# Electronic_DC_Load.net
KiCad netlist of a schematic drawn in EAGLE
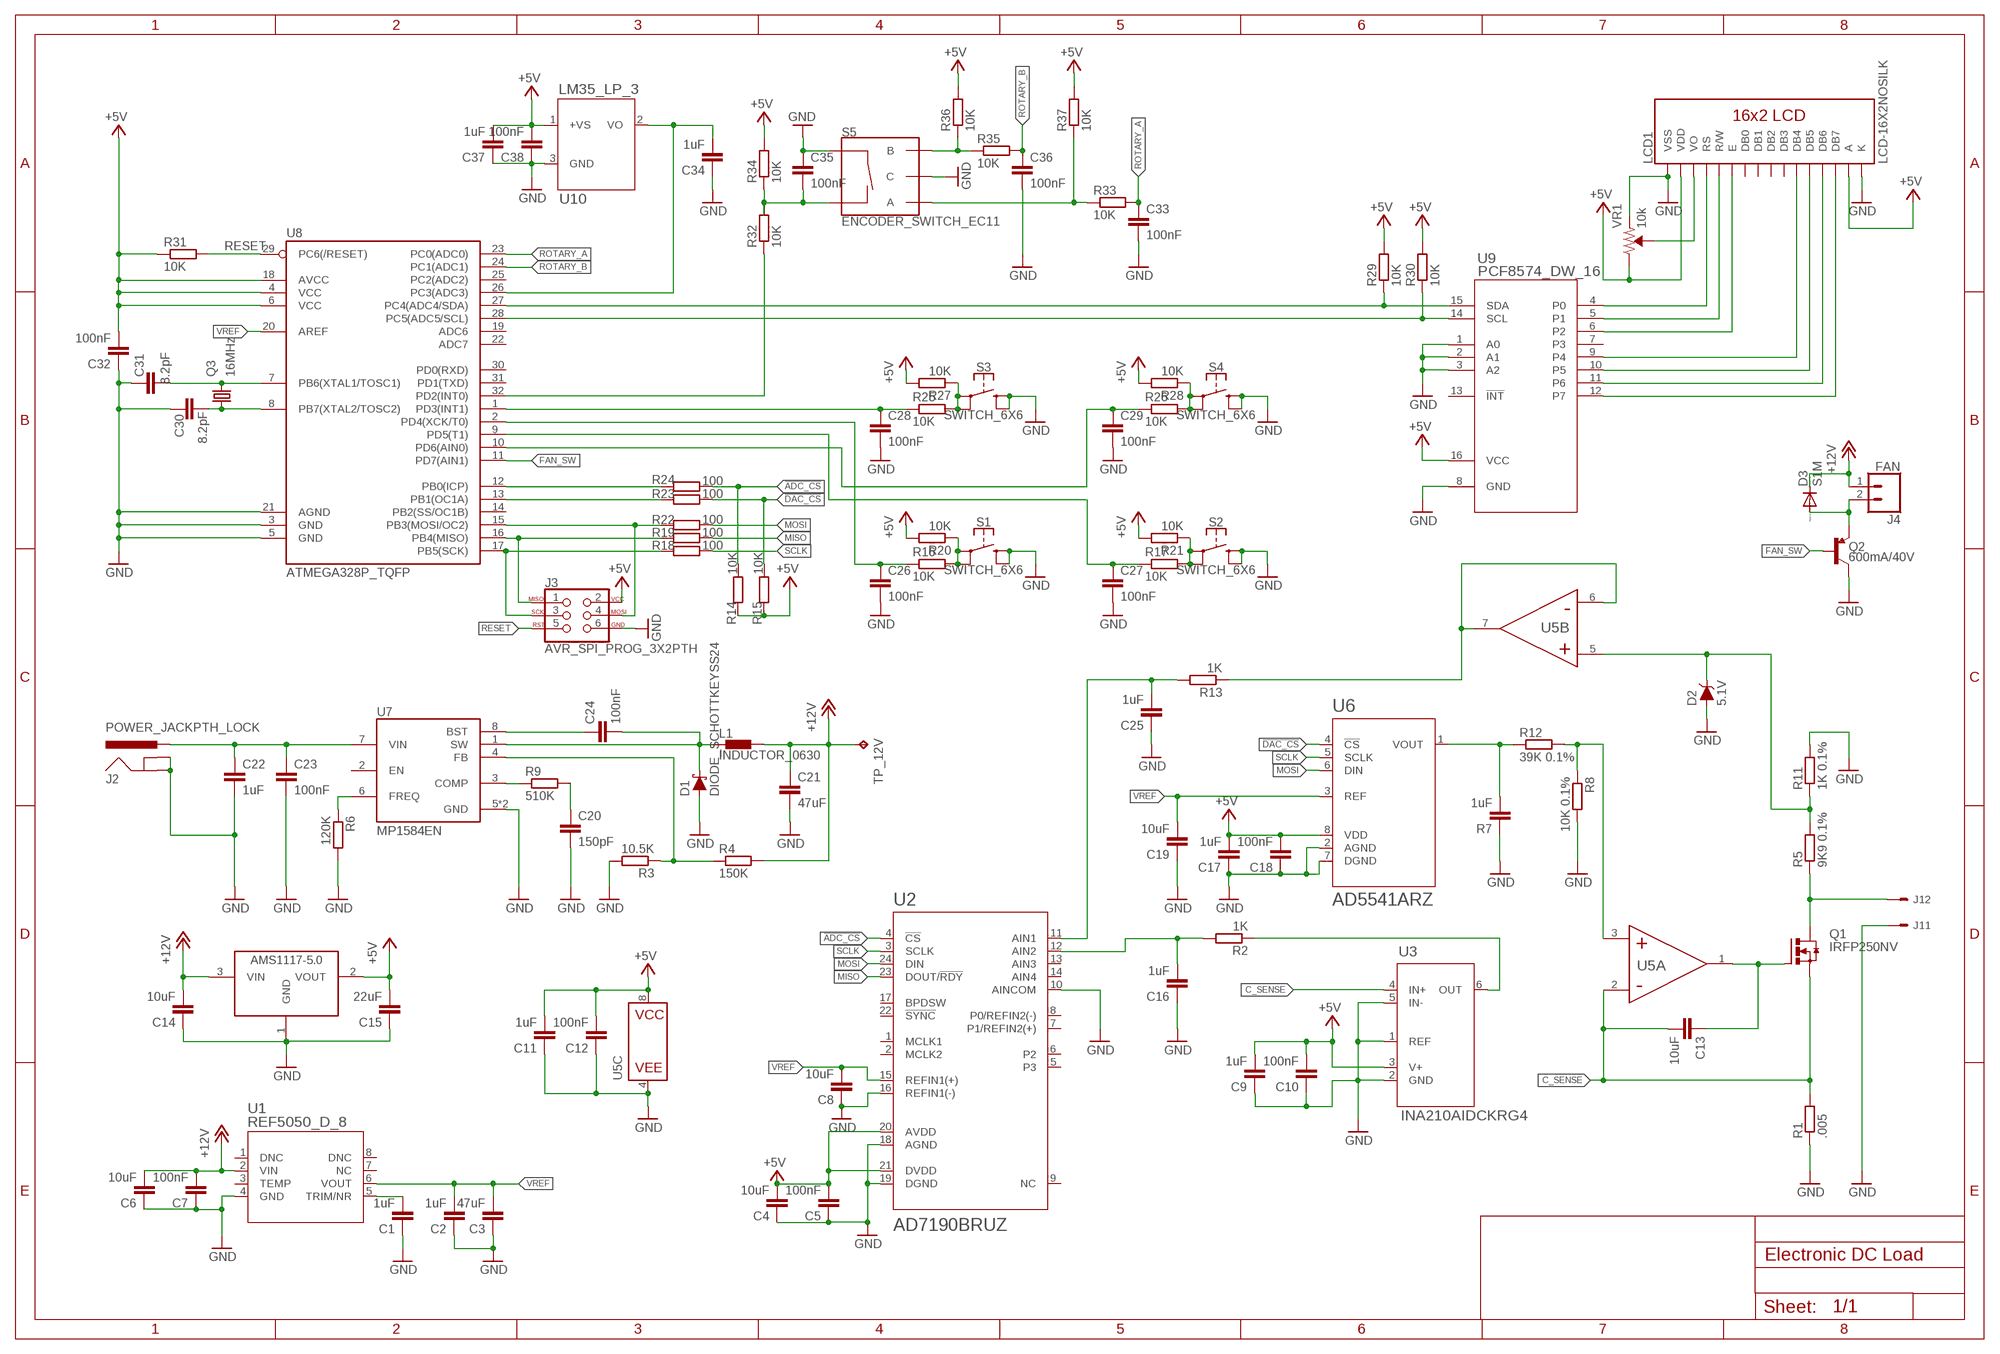
[diagram p0: schematic, sheet 1]

(export (version "E")
  (design (tool "Eeschema 10.0.6"))
  (components
    (comp (ref "C1")
      (value "1uF")
      (footprint "eagle-import:C0805")
      (libsource (lib "eagle-import") (part "C-EUC0805"))
    )
    (comp (ref "C2")
      (value "1uF")
      (footprint "eagle-import:C0805")
      (libsource (lib "eagle-import") (part "C-EUC0805"))
    )
    (comp (ref "C3")
      (value "47uF")
      (footprint "eagle-import:C1206")
      (libsource (lib "eagle-import") (part "C-EUC1206"))
    )
    (comp (ref "C4")
      (value "10uF")
      (footprint "eagle-import:C1206")
      (libsource (lib "eagle-import") (part "C-EUC1206"))
    )
    (comp (ref "C5")
      (value "100nF")
      (footprint "eagle-import:C0805")
      (libsource (lib "eagle-import") (part "C-EUC0805"))
    )
    (comp (ref "C6")
      (value "10uF")
      (footprint "eagle-import:C1206")
      (libsource (lib "eagle-import") (part "C-EUC1206"))
    )
    (comp (ref "C7")
      (value "100nF")
      (footprint "eagle-import:C0805")
      (libsource (lib "eagle-import") (part "C-EUC0805"))
    )
    (comp (ref "C8")
      (value "10uF")
      (footprint "eagle-import:C1206")
      (libsource (lib "eagle-import") (part "C-EUC1206"))
    )
    (comp (ref "C9")
      (value "1uF")
      (footprint "eagle-import:C0805")
      (libsource (lib "eagle-import") (part "C-EUC0805"))
    )
    (comp (ref "C10")
      (value "100nF")
      (footprint "eagle-import:C0805")
      (libsource (lib "eagle-import") (part "C-EUC0805"))
    )
    (comp (ref "C11")
      (value "1uF")
      (footprint "eagle-import:C0805")
      (libsource (lib "eagle-import") (part "C-EUC0805"))
    )
    (comp (ref "C12")
      (value "100nF")
      (footprint "eagle-import:C0805")
      (libsource (lib "eagle-import") (part "C-EUC0805"))
    )
    (comp (ref "C13")
      (value "10uF")
      (footprint "eagle-import:C1206")
      (libsource (lib "eagle-import") (part "C-EUC1206"))
    )
    (comp (ref "C14")
      (value "10uF")
      (footprint "eagle-import:C1206")
      (libsource (lib "eagle-import") (part "C-EUC1206"))
    )
    (comp (ref "C15")
      (value "22uF")
      (footprint "eagle-import:C1206")
      (libsource (lib "eagle-import") (part "C-EUC1206"))
    )
    (comp (ref "C16")
      (value "1uF")
      (footprint "eagle-import:C0805")
      (libsource (lib "eagle-import") (part "C-EUC0805"))
    )
    (comp (ref "C17")
      (value "1uF")
      (footprint "eagle-import:C0805")
      (libsource (lib "eagle-import") (part "C-EUC0805"))
    )
    (comp (ref "C18")
      (value "100nF")
      (footprint "eagle-import:C0805")
      (libsource (lib "eagle-import") (part "C-EUC0805"))
    )
    (comp (ref "C19")
      (value "10uF")
      (footprint "eagle-import:C1206")
      (libsource (lib "eagle-import") (part "C-EUC1206"))
    )
    (comp (ref "C20")
      (value "150pF")
      (footprint "eagle-import:C0402")
      (libsource (lib "eagle-import") (part "C-EUC0402"))
    )
    (comp (ref "C21")
      (value "47uF")
      (footprint "eagle-import:C1206")
      (libsource (lib "eagle-import") (part "C-EUC1206"))
    )
    (comp (ref "C22")
      (value "1uF")
      (footprint "eagle-import:C0805")
      (libsource (lib "eagle-import") (part "C-EUC0805"))
    )
    (comp (ref "C23")
      (value "100nF")
      (footprint "eagle-import:C0805")
      (libsource (lib "eagle-import") (part "C-EUC0805"))
    )
    (comp (ref "C24")
      (value "100nF")
      (footprint "eagle-import:C0805")
      (libsource (lib "eagle-import") (part "C-EUC0805"))
    )
    (comp (ref "C25")
      (value "1uF")
      (footprint "eagle-import:C0805")
      (libsource (lib "eagle-import") (part "C-EUC0805"))
    )
    (comp (ref "C26")
      (value "100nF")
      (footprint "eagle-import:C0603")
      (libsource (lib "eagle-import") (part "C-EUC0603"))
    )
    (comp (ref "C27")
      (value "100nF")
      (footprint "eagle-import:C0603")
      (libsource (lib "eagle-import") (part "C-EUC0603"))
    )
    (comp (ref "C28")
      (value "100nF")
      (footprint "eagle-import:C0603")
      (libsource (lib "eagle-import") (part "C-EUC0603"))
    )
    (comp (ref "C29")
      (value "100nF")
      (footprint "eagle-import:C0603")
      (libsource (lib "eagle-import") (part "C-EUC0603"))
    )
    (comp (ref "C30")
      (value "8.2pF")
      (footprint "eagle-import:C0603")
      (libsource (lib "eagle-import") (part "C-EUC0603"))
    )
    (comp (ref "C31")
      (value "8.2pF")
      (footprint "eagle-import:C0603")
      (libsource (lib "eagle-import") (part "C-EUC0603"))
    )
    (comp (ref "C32")
      (value "100nF")
      (footprint "eagle-import:C0603")
      (libsource (lib "eagle-import") (part "C-EUC0603"))
    )
    (comp (ref "C33")
      (value "100nF")
      (footprint "eagle-import:C0603")
      (libsource (lib "eagle-import") (part "C-EUC0603"))
    )
    (comp (ref "C34")
      (value "1uF")
      (footprint "eagle-import:C0805")
      (libsource (lib "eagle-import") (part "C-EUC0805"))
    )
    (comp (ref "C35")
      (value "100nF")
      (footprint "eagle-import:C0603")
      (libsource (lib "eagle-import") (part "C-EUC0603"))
    )
    (comp (ref "C36")
      (value "100nF")
      (footprint "eagle-import:C0603")
      (libsource (lib "eagle-import") (part "C-EUC0603"))
    )
    (comp (ref "C37")
      (value "1uF")
      (footprint "eagle-import:C0805")
      (libsource (lib "eagle-import") (part "C-EUC0805"))
    )
    (comp (ref "C38")
      (value "100nF")
      (footprint "eagle-import:C0805")
      (libsource (lib "eagle-import") (part "C-EUC0805"))
    )
    (comp (ref "D1")
      (value "DIODE_SCHOTTKEYSS24")
      (footprint "eagle-import:SMA-DIODE")
      (libsource (lib "eagle-import") (part "DIODE_SCHOTTKEYSS24"))
    )
    (comp (ref "D2")
      (value "5.1V")
      (footprint "eagle-import:LL-34")
      (libsource (lib "eagle-import") (part "DIODE-ZENER-ZMM5.1"))
    )
    (comp (ref "D3")
      (value "S1M")
      (footprint "eagle-import:SMA")
      (libsource (lib "eagle-import") (part "S1M"))
    )
    (comp (ref "J1")
      (value "KF762-2")
      (footprint "eagle-import:KF762-2")
      (libsource (lib "eagle-import") (part "KF762-2"))
    )
    (comp (ref "J2")
      (value "POWER_JACKPTH_LOCK")
      (footprint "eagle-import:POWER_JACK_PTH_LOCK")
      (libsource (lib "eagle-import") (part "POWER_JACKPTH_LOCK"))
    )
    (comp (ref "J3")
      (value "AVR_SPI_PROG_3X2PTH")
      (footprint "eagle-import:2X3")
      (libsource (lib "eagle-import") (part "AVR_SPI_PROG_3X2PTH"))
    )
    (comp (ref "J4")
      (value "FAN")
      (footprint "eagle-import:1X02_LOCK_LONGPADS")
      (libsource (lib "eagle-import") (part "CONN_02LOCK_LONGPADS"))
    )
    (comp (ref "L1")
      (value "INDUCTOR_0630")
      (footprint "eagle-import:INDUCTOR_0630")
      (libsource (lib "eagle-import") (part "INDUCTOR_0630"))
    )
    (comp (ref "LCD1")
      (value "LCD-16X2NOSILK")
      (footprint "eagle-import:LCD-16X2_NOSILK")
      (libsource (lib "eagle-import") (part "LCD-16X2NOSILK"))
    )
    (comp (ref "Q1")
      (value "IRFP250NV")
      (footprint "eagle-import:TO247BV")
      (libsource (lib "eagle-import") (part "IRFP250NV"))
    )
    (comp (ref "Q2")
      (value "600mA/40V")
      (footprint "eagle-import:SOT23-3")
      (libsource (lib "eagle-import") (part "TRANS_PNP-MMBT4403"))
    )
    (comp (ref "Q3")
      (value "16MHz")
      (footprint "eagle-import:3.2X2.5_KX-7")
      (libsource (lib "eagle-import") (part "KX-7"))
    )
    (comp (ref "R1")
      (value ".005")
      (footprint "eagle-import:2728")
      (libsource (lib "eagle-import") (part "MRE_R005_4W_2728_1%"))
    )
    (comp (ref "R2")
      (value "1K")
      (footprint "eagle-import:R0805")
      (libsource (lib "eagle-import") (part "R-EU_R0805"))
    )
    (comp (ref "R3")
      (value "10.5K")
      (footprint "eagle-import:R0603")
      (libsource (lib "eagle-import") (part "R-EU_R0603"))
    )
    (comp (ref "R4")
      (value "150K")
      (footprint "eagle-import:R0603")
      (libsource (lib "eagle-import") (part "R-EU_R0603"))
    )
    (comp (ref "R5")
      (value "9K9 0.1%")
      (footprint "eagle-import:M0805")
      (libsource (lib "eagle-import") (part "R-EU_M0805"))
    )
    (comp (ref "R6")
      (value "120K")
      (footprint "eagle-import:R0603")
      (libsource (lib "eagle-import") (part "R-EU_R0603"))
    )
    (comp (ref "R7")
      (value "1uF")
      (footprint "eagle-import:C0805")
      (libsource (lib "eagle-import") (part "C-EUC0805"))
    )
    (comp (ref "R8")
      (value "10K 0.1%")
      (footprint "eagle-import:R0805")
      (libsource (lib "eagle-import") (part "R-EU_R0805"))
    )
    (comp (ref "R9")
      (value "510K")
      (footprint "eagle-import:R0603")
      (libsource (lib "eagle-import") (part "R-EU_R0603"))
    )
    (comp (ref "R11")
      (value "1K 0.1%")
      (footprint "eagle-import:M0805")
      (libsource (lib "eagle-import") (part "R-EU_M0805"))
    )
    (comp (ref "R12")
      (value "39K 0.1%")
      (footprint "eagle-import:R0805")
      (libsource (lib "eagle-import") (part "R-EU_R0805"))
    )
    (comp (ref "R13")
      (value "1K")
      (footprint "eagle-import:R0805")
      (libsource (lib "eagle-import") (part "R-EU_R0805"))
    )
    (comp (ref "R14")
      (value "10K")
      (footprint "eagle-import:M0805")
      (libsource (lib "eagle-import") (part "R-EU_M0805"))
    )
    (comp (ref "R15")
      (value "10K")
      (footprint "eagle-import:M0805")
      (libsource (lib "eagle-import") (part "R-EU_M0805"))
    )
    (comp (ref "R16")
      (value "10K")
      (footprint "eagle-import:R0603")
      (libsource (lib "eagle-import") (part "R-EU_R0603"))
    )
    (comp (ref "R17")
      (value "10K")
      (footprint "eagle-import:R0603")
      (libsource (lib "eagle-import") (part "R-EU_R0603"))
    )
    (comp (ref "R18")
      (value "100")
      (footprint "eagle-import:M0805")
      (libsource (lib "eagle-import") (part "R-EU_M0805"))
    )
    (comp (ref "R19")
      (value "100")
      (footprint "eagle-import:M0805")
      (libsource (lib "eagle-import") (part "R-EU_M0805"))
    )
    (comp (ref "R20")
      (value "10K")
      (footprint "eagle-import:R0603")
      (libsource (lib "eagle-import") (part "R-EU_R0603"))
    )
    (comp (ref "R21")
      (value "10K")
      (footprint "eagle-import:R0603")
      (libsource (lib "eagle-import") (part "R-EU_R0603"))
    )
    (comp (ref "R22")
      (value "100")
      (footprint "eagle-import:M0805")
      (libsource (lib "eagle-import") (part "R-EU_M0805"))
    )
    (comp (ref "R23")
      (value "100")
      (footprint "eagle-import:M0805")
      (libsource (lib "eagle-import") (part "R-EU_M0805"))
    )
    (comp (ref "R24")
      (value "100")
      (footprint "eagle-import:M0805")
      (libsource (lib "eagle-import") (part "R-EU_M0805"))
    )
    (comp (ref "R25")
      (value "10K")
      (footprint "eagle-import:R0603")
      (libsource (lib "eagle-import") (part "R-EU_R0603"))
    )
    (comp (ref "R26")
      (value "10K")
      (footprint "eagle-import:R0603")
      (libsource (lib "eagle-import") (part "R-EU_R0603"))
    )
    (comp (ref "R27")
      (value "10K")
      (footprint "eagle-import:R0603")
      (libsource (lib "eagle-import") (part "R-EU_R0603"))
    )
    (comp (ref "R28")
      (value "10K")
      (footprint "eagle-import:R0603")
      (libsource (lib "eagle-import") (part "R-EU_R0603"))
    )
    (comp (ref "R29")
      (value "10K")
      (footprint "eagle-import:R0603")
      (libsource (lib "eagle-import") (part "R-EU_R0603"))
    )
    (comp (ref "R30")
      (value "10K")
      (footprint "eagle-import:R0603")
      (libsource (lib "eagle-import") (part "R-EU_R0603"))
    )
    (comp (ref "R31")
      (value "10K")
      (footprint "eagle-import:R0603")
      (libsource (lib "eagle-import") (part "R-EU_R0603"))
    )
    (comp (ref "R32")
      (value "10K")
      (footprint "eagle-import:R0603")
      (libsource (lib "eagle-import") (part "R-EU_R0603"))
    )
    (comp (ref "R33")
      (value "10K")
      (footprint "eagle-import:R0603")
      (libsource (lib "eagle-import") (part "R-EU_R0603"))
    )
    (comp (ref "R34")
      (value "10K")
      (footprint "eagle-import:R0603")
      (libsource (lib "eagle-import") (part "R-EU_R0603"))
    )
    (comp (ref "R35")
      (value "10K")
      (footprint "eagle-import:R0603")
      (libsource (lib "eagle-import") (part "R-EU_R0603"))
    )
    (comp (ref "R36")
      (value "10K")
      (footprint "eagle-import:R0603")
      (libsource (lib "eagle-import") (part "R-EU_R0603"))
    )
    (comp (ref "R37")
      (value "10K")
      (footprint "eagle-import:R0603")
      (libsource (lib "eagle-import") (part "R-EU_R0603"))
    )
    (comp (ref "S1")
      (value "SWITCH_6X6")
      (footprint "eagle-import:SWITCH_SMD_6MM")
      (libsource (lib "eagle-import") (part "SWITCH_6X6"))
    )
    (comp (ref "S2")
      (value "SWITCH_6X6")
      (footprint "eagle-import:SWITCH_SMD_6MM")
      (libsource (lib "eagle-import") (part "SWITCH_6X6"))
    )
    (comp (ref "S3")
      (value "SWITCH_6X6")
      (footprint "eagle-import:SWITCH_SMD_6MM")
      (libsource (lib "eagle-import") (part "SWITCH_6X6"))
    )
    (comp (ref "S4")
      (value "SWITCH_6X6")
      (footprint "eagle-import:SWITCH_SMD_6MM")
      (libsource (lib "eagle-import") (part "SWITCH_6X6"))
    )
    (comp (ref "S5")
      (value "ENCODER_SWITCH_EC11")
      (footprint "eagle-import:ROTARY_ENCODER_EC11")
      (libsource (lib "eagle-import") (part "ENCODER_SWITCH_EC11"))
    )
    (comp (ref "TP_12V")
      (value "TPB1,27")
      (footprint "eagle-import:B1,27")
      (libsource (lib "eagle-import") (part "TPB1,27"))
    )
    (comp (ref "U1")
      (value "REF5050_D_8")
      (footprint "eagle-import:D8")
      (fields
        (field (name "GENERIC_PART_NUMBER") "REF5050")
        (field (name "MANUFACTURER") "Texas Instruments")
        (field (name "MANUFACTURER_PART_NUMBER") "ref5050_d_8")
      )
      (libsource (lib "eagle-import") (part "REF5050_D_8"))
    )
    (comp (ref "U2")
      (value "AD7190BRUZ")
      (footprint "eagle-import:RU_24")
      (fields (field (name "MANUFACTURER_PART_NUMBER") "AD7190BRUZREEL"))
      (libsource (lib "eagle-import") (part "AD7190BRUZ"))
    )
    (comp (ref "U3")
      (value "INA210AIDCKRG4")
      (footprint "eagle-import:DCK0006A_N")
      (fields
        (field (name "ALTERNATEPARTNUMBER") "INA210AIDCKT")
        (field (name "MANUFACTURER") "Texas Instruments")
        (field (name "PARTNUMBER") "INA210AIDCKR")
      )
      (libsource (lib "eagle-import") (part "INA210AIDCKRG4"))
    )
    (comp (ref "U4")
      (value "AMS1117-5.0")
      (footprint "eagle-import:SOT223")
      (fields (field (name "MF") "ams"))
      (libsource (lib "eagle-import") (part "AMS1117-5.0"))
    )
    (comp (ref "U5")
      (value "AD8629ARZ")
      (footprint "eagle-import:R_8")
      (libsource (lib "eagle-import") (part "AD8629ARZ"))
    )
    (comp (ref "U6")
      (value "AD5541ARZ")
      (footprint "eagle-import:R_8")
      (libsource (lib "eagle-import") (part "AD5541ARZ"))
    )
    (comp (ref "U7")
      (value "MP1584EN")
      (footprint "eagle-import:SOIC9P127_490X600X170L84X42T330X241N")
      (fields (field (name "MF") "Monolithic Power Systems"))
      (libsource (lib "eagle-import") (part "MP1584EN"))
    )
    (comp (ref "U8")
      (value "ATMEGA328P_TQFP")
      (footprint "eagle-import:TQFP32-08")
      (libsource (lib "eagle-import") (part "ATMEGA328P_TQFP"))
    )
    (comp (ref "U9")
      (value "PCF8574_DW_16")
      (footprint "eagle-import:DW16")
      (fields (field (name "MANUFACTURER_PART_NUMBER") "pcf8574_dw_16"))
      (libsource (lib "eagle-import") (part "PCF8574_DW_16"))
    )
    (comp (ref "U10")
      (value "LM35_LP_3")
      (footprint "eagle-import:Z03A")
      (libsource (lib "eagle-import") (part "LM35_LP_3"))
    )
    (comp (ref "VR1")
      (value "10k")
      (footprint "eagle-import:TRIMPOT-SMD-TC33X")
      (libsource (lib "eagle-import") (part "TRIMPOT-SMD-3MM-OPEN-1/10W-25%"))
    )
  )
  (nets
    (net (code "1") (name "+5V") (class "Default")
      (node (ref "C10") (pin "2") (pinfunction "2_2") (pintype "passive"))
      (node (ref "C11") (pin "2") (pinfunction "2_2") (pintype "passive"))
      (node (ref "C12") (pin "2") (pinfunction "2_2") (pintype "passive"))
      (node (ref "C15") (pin "2") (pinfunction "2_2") (pintype "passive"))
      (node (ref "C17") (pin "2") (pinfunction "2_2") (pintype "passive"))
      (node (ref "C18") (pin "2") (pinfunction "2_2") (pintype "passive"))
      (node (ref "C32") (pin "2") (pinfunction "2_2") (pintype "passive"))
      (node (ref "C37") (pin "2") (pinfunction "2_2") (pintype "passive"))
      (node (ref "C38") (pin "2") (pinfunction "2_2") (pintype "passive"))
      (node (ref "C4") (pin "2") (pinfunction "2_2") (pintype "passive"))
      (node (ref "C5") (pin "2") (pinfunction "2_2") (pintype "passive"))
      (node (ref "C9") (pin "2") (pinfunction "2_2") (pintype "passive"))
      (node (ref "J3") (pin "2") (pinfunction "2_2") (pintype "passive"))
      (node (ref "LCD1") (pin "15") (pinfunction "A_15") (pintype "power_in"))
      (node (ref "LCD1") (pin "2") (pinfunction "VDD_2") (pintype "power_in"))
      (node (ref "R14") (pin "1") (pinfunction "1_1") (pintype "passive"))
      (node (ref "R15") (pin "1") (pinfunction "1_1") (pintype "passive"))
      (node (ref "R20") (pin "2") (pinfunction "2_2") (pintype "passive"))
      (node (ref "R21") (pin "2") (pinfunction "2_2") (pintype "passive"))
      (node (ref "R27") (pin "2") (pinfunction "2_2") (pintype "passive"))
      (node (ref "R28") (pin "2") (pinfunction "2_2") (pintype "passive"))
      (node (ref "R29") (pin "2") (pinfunction "2_2") (pintype "passive"))
      (node (ref "R30") (pin "2") (pinfunction "2_2") (pintype "passive"))
      (node (ref "R31") (pin "1") (pinfunction "1_1") (pintype "passive"))
      (node (ref "R34") (pin "2") (pinfunction "2_2") (pintype "passive"))
      (node (ref "R36") (pin "2") (pinfunction "2_2") (pintype "passive"))
      (node (ref "R37") (pin "2") (pinfunction "2_2") (pintype "passive"))
      (node (ref "U10") (pin "1") (pinfunction "+VS_1") (pintype "power_in"))
      (node (ref "U2") (pin "20") (pinfunction "AVDD_20") (pintype "power_in"))
      (node (ref "U2") (pin "21") (pinfunction "DVDD_21") (pintype "power_in"))
      (node (ref "U3") (pin "3") (pinfunction "V+_3") (pintype "power_in"))
      (node (ref "U4") (pin "2") (pinfunction "VOUT_2") (pintype "bidirectional"))
      (node (ref "U5") (pin "8") (pinfunction "VCC_8") (pintype "power_in"))
      (node (ref "U6") (pin "8") (pinfunction "VDD_8") (pintype "power_in"))
      (node (ref "U8") (pin "18") (pinfunction "AVCC_18") (pintype "bidirectional"))
      (node (ref "U8") (pin "4") (pinfunction "VCC_4") (pintype "bidirectional"))
      (node (ref "U8") (pin "6") (pinfunction "VCC_6") (pintype "bidirectional"))
      (node (ref "U9") (pin "16") (pinfunction "VCC_16") (pintype "power_in"))
      (node (ref "VR1") (pin "1") (pinfunction "CW_1") (pintype "passive"))
    )
    (net (code "2") (name "+12V") (class "Default")
      (node (ref "C14") (pin "2") (pinfunction "2_2") (pintype "passive"))
      (node (ref "C21") (pin "1") (pinfunction "1_1") (pintype "passive"))
      (node (ref "C6") (pin "2") (pinfunction "2_2") (pintype "passive"))
      (node (ref "C7") (pin "2") (pinfunction "2_2") (pintype "passive"))
      (node (ref "D3") (pin "C") (pinfunction "C_C") (pintype "passive"))
      (node (ref "J4") (pin "1") (pinfunction "1_1") (pintype "passive"))
      (node (ref "L1") (pin "P$2") (pinfunction "2_P$2") (pintype "passive"))
      (node (ref "R4") (pin "2") (pinfunction "2_2") (pintype "passive"))
      (node (ref "TP_12V") (pin "TP") (pinfunction "TP_TP") (pintype "input"))
      (node (ref "U1") (pin "2") (pinfunction "VIN_2") (pintype "input"))
      (node (ref "U4") (pin "3") (pinfunction "VIN_3") (pintype "bidirectional"))
    )
    (net (code "3") (name "/~{ADC_CS}") (class "Default")
      (node (ref "R14") (pin "2") (pinfunction "2_2") (pintype "passive"))
      (node (ref "R24") (pin "2") (pinfunction "2_2") (pintype "passive"))
      (node (ref "U2") (pin "4") (pinfunction "~{CS}_4") (pintype "passive"))
    )
    (net (code "4") (name "/~{DAC_CS}") (class "Default")
      (node (ref "R15") (pin "2") (pinfunction "2_2") (pintype "passive"))
      (node (ref "R23") (pin "2") (pinfunction "2_2") (pintype "passive"))
      (node (ref "U6") (pin "4") (pinfunction "~{CS}_4") (pintype "passive"))
    )
    (net (code "5") (name "C_SENSE") (class "Default")
      (node (ref "C13") (pin "2") (pinfunction "2_2") (pintype "passive"))
      (node (ref "Q1") (pin "S") (pinfunction "S_S") (pintype "passive"))
      (node (ref "R1") (pin "2") (pinfunction "2_2") (pintype "passive"))
      (node (ref "U3") (pin "4") (pinfunction "IN+_4") (pintype "input"))
      (node (ref "U5") (pin "2") (pinfunction "IN-_2") (pintype "passive"))
    )
    (net (code "6") (name "FAN_SW") (class "Default")
      (node (ref "Q2") (pin "1") (pinfunction "B_1") (pintype "passive"))
      (node (ref "U8") (pin "11") (pinfunction "PD7(AIN1)_11") (pintype "bidirectional"))
    )
    (net (code "7") (name "GND") (class "Default")
      (node (ref "C1") (pin "1") (pinfunction "1_1") (pintype "passive"))
      (node (ref "C10") (pin "1") (pinfunction "1_1") (pintype "passive"))
      (node (ref "C11") (pin "1") (pinfunction "1_1") (pintype "passive"))
      (node (ref "C12") (pin "1") (pinfunction "1_1") (pintype "passive"))
      (node (ref "C14") (pin "1") (pinfunction "1_1") (pintype "passive"))
      (node (ref "C15") (pin "1") (pinfunction "1_1") (pintype "passive"))
      (node (ref "C16") (pin "1") (pinfunction "1_1") (pintype "passive"))
      (node (ref "C17") (pin "1") (pinfunction "1_1") (pintype "passive"))
      (node (ref "C18") (pin "1") (pinfunction "1_1") (pintype "passive"))
      (node (ref "C19") (pin "1") (pinfunction "1_1") (pintype "passive"))
      (node (ref "C2") (pin "1") (pinfunction "1_1") (pintype "passive"))
      (node (ref "C20") (pin "2") (pinfunction "2_2") (pintype "passive"))
      (node (ref "C21") (pin "2") (pinfunction "2_2") (pintype "passive"))
      (node (ref "C22") (pin "2") (pinfunction "2_2") (pintype "passive"))
      (node (ref "C23") (pin "2") (pinfunction "2_2") (pintype "passive"))
      (node (ref "C25") (pin "1") (pinfunction "1_1") (pintype "passive"))
      (node (ref "C26") (pin "2") (pinfunction "2_2") (pintype "passive"))
      (node (ref "C27") (pin "2") (pinfunction "2_2") (pintype "passive"))
      (node (ref "C28") (pin "2") (pinfunction "2_2") (pintype "passive"))
      (node (ref "C29") (pin "2") (pinfunction "2_2") (pintype "passive"))
      (node (ref "C3") (pin "1") (pinfunction "1_1") (pintype "passive"))
      (node (ref "C30") (pin "1") (pinfunction "1_1") (pintype "passive"))
      (node (ref "C31") (pin "1") (pinfunction "1_1") (pintype "passive"))
      (node (ref "C32") (pin "1") (pinfunction "1_1") (pintype "passive"))
      (node (ref "C33") (pin "2") (pinfunction "2_2") (pintype "passive"))
      (node (ref "C34") (pin "1") (pinfunction "1_1") (pintype "passive"))
      (node (ref "C35") (pin "1") (pinfunction "1_1") (pintype "passive"))
      (node (ref "C36") (pin "2") (pinfunction "2_2") (pintype "passive"))
      (node (ref "C37") (pin "1") (pinfunction "1_1") (pintype "passive"))
      (node (ref "C38") (pin "1") (pinfunction "1_1") (pintype "passive"))
      (node (ref "C4") (pin "1") (pinfunction "1_1") (pintype "passive"))
      (node (ref "C5") (pin "1") (pinfunction "1_1") (pintype "passive"))
      (node (ref "C6") (pin "1") (pinfunction "1_1") (pintype "passive"))
      (node (ref "C7") (pin "1") (pinfunction "1_1") (pintype "passive"))
      (node (ref "C8") (pin "1") (pinfunction "1_1") (pintype "passive"))
      (node (ref "C9") (pin "1") (pinfunction "1_1") (pintype "passive"))
      (node (ref "D1") (pin "A") (pinfunction "A_A") (pintype "passive"))
      (node (ref "D2") (pin "A") (pinfunction "A_A") (pintype "passive"))
      (node (ref "J1") (pin "1") (pinfunction "S_1") (pintype "passive"))
      (node (ref "J2") (pin "GND") (pinfunction "GND_GND") (pintype "bidirectional"))
      (node (ref "J2") (pin "GNDBREAK") (pinfunction "GNDBREAK_GNDBREAK") (pintype "bidirectional"))
      (node (ref "J3") (pin "6") (pinfunction "6_6") (pintype "passive"))
      (node (ref "LCD1") (pin "1") (pinfunction "VSS_1") (pintype "power_in"))
      (node (ref "LCD1") (pin "16") (pinfunction "K_16") (pintype "power_in"))
      (node (ref "Q2") (pin "3") (pinfunction "C_3") (pintype "passive"))
      (node (ref "R1") (pin "1") (pinfunction "1_1") (pintype "passive"))
      (node (ref "R11") (pin "2") (pinfunction "2_2") (pintype "passive"))
      (node (ref "R3") (pin "2") (pinfunction "2_2") (pintype "passive"))
      (node (ref "R6") (pin "2") (pinfunction "2_2") (pintype "passive"))
      (node (ref "R7") (pin "1") (pinfunction "1_1") (pintype "passive"))
      (node (ref "R8") (pin "2") (pinfunction "2_2") (pintype "passive"))
      (node (ref "S1") (pin "B1") (pinfunction "3_B1") (pintype "passive"))
      (node (ref "S1") (pin "B2") (pinfunction "4_B2") (pintype "passive"))
      (node (ref "S2") (pin "B1") (pinfunction "3_B1") (pintype "passive"))
      (node (ref "S2") (pin "B2") (pinfunction "4_B2") (pintype "passive"))
      (node (ref "S3") (pin "B1") (pinfunction "3_B1") (pintype "passive"))
      (node (ref "S3") (pin "B2") (pinfunction "4_B2") (pintype "passive"))
      (node (ref "S4") (pin "B1") (pinfunction "3_B1") (pintype "passive"))
      (node (ref "S4") (pin "B2") (pinfunction "4_B2") (pintype "passive"))
      (node (ref "S5") (pin "C") (pinfunction "C_C") (pintype "bidirectional"))
      (node (ref "S5") (pin "D") (pinfunction "SW+_D") (pintype "bidirectional"))
      (node (ref "U1") (pin "4") (pinfunction "GND_4") (pintype "power_in"))
      (node (ref "U10") (pin "3") (pinfunction "GND_3") (pintype "power_in"))
      (node (ref "U2") (pin "10") (pinfunction "AINCOM_10") (pintype "passive"))
      (node (ref "U2") (pin "16") (pinfunction "REFIN1(-)_16") (pintype "passive"))
      (node (ref "U2") (pin "18") (pinfunction "AGND_18") (pintype "passive"))
      (node (ref "U2") (pin "19") (pinfunction "DGND_19") (pintype "passive"))
      (node (ref "U3") (pin "1") (pinfunction "REF_1") (pintype "input"))
      (node (ref "U3") (pin "2") (pinfunction "GND_2") (pintype "power_in"))
      (node (ref "U3") (pin "5") (pinfunction "IN-_5") (pintype "input"))
      (node (ref "U4") (pin "1") (pinfunction "GND_1") (pintype "bidirectional"))
      (node (ref "U5") (pin "4") (pinfunction "VEE_4") (pintype "power_in"))
      (node (ref "U6") (pin "2") (pinfunction "AGND_2") (pintype "passive"))
      (node (ref "U6") (pin "7") (pinfunction "DGND_7") (pintype "passive"))
      (node (ref "U7") (pin "5") (pinfunction "GND_5") (pintype "power_in"))
      (node (ref "U7") (pin "9") (pinfunction "GND_9") (pintype "power_in"))
      (node (ref "U8") (pin "21") (pinfunction "AGND_21") (pintype "bidirectional"))
      (node (ref "U8") (pin "3") (pinfunction "GND_3") (pintype "bidirectional"))
      (node (ref "U8") (pin "5") (pinfunction "GND_5") (pintype "bidirectional"))
      (node (ref "U9") (pin "1") (pinfunction "A0_1") (pintype "input"))
      (node (ref "U9") (pin "2") (pinfunction "A1_2") (pintype "input"))
      (node (ref "U9") (pin "3") (pinfunction "A2_3") (pintype "input"))
      (node (ref "U9") (pin "8") (pinfunction "GND_8") (pintype "power_in"))
      (node (ref "VR1") (pin "3") (pinfunction "CCW_3") (pintype "passive"))
    )
    (net (code "8") (name "MISO") (class "Default")
      (node (ref "R19") (pin "2") (pinfunction "2_2") (pintype "passive"))
      (node (ref "U2") (pin "23") (pinfunction "DOUT/~{RDY}_23") (pintype "passive"))
    )
    (net (code "9") (name "MOSI") (class "Default")
      (node (ref "R22") (pin "2") (pinfunction "2_2") (pintype "passive"))
      (node (ref "U2") (pin "24") (pinfunction "DIN_24") (pintype "passive"))
      (node (ref "U6") (pin "6") (pinfunction "DIN_6") (pintype "passive"))
    )
    (net (code "10") (name "Net-(C20-Pad1)") (class "Default")
      (node (ref "C20") (pin "1") (pinfunction "1_1") (pintype "passive"))
      (node (ref "R9") (pin "2") (pinfunction "2_2") (pintype "passive"))
    )
    (net (code "11") (name "Net-(J1B-S)") (class "Default")
      (node (ref "J1") (pin "2") (pinfunction "S_2") (pintype "passive"))
      (node (ref "Q1") (pin "D") (pinfunction "D_D") (pintype "passive"))
      (node (ref "R5") (pin "1") (pinfunction "1_1") (pintype "passive"))
    )
    (net (code "12") (name "Net-(L1-1)") (class "Default")
      (node (ref "C24") (pin "2") (pinfunction "2_2") (pintype "passive"))
      (node (ref "D1") (pin "C") (pinfunction "C_C") (pintype "passive"))
      (node (ref "L1") (pin "P$1") (pinfunction "1_P$1") (pintype "passive"))
      (node (ref "U7") (pin "1") (pinfunction "SW_1") (pintype "output"))
    )
    (net (code "13") (name "Net-(LCD1-DB4)") (class "Default")
      (node (ref "LCD1") (pin "11") (pinfunction "DB4_11") (pintype "bidirectional"))
      (node (ref "U9") (pin "9") (pinfunction "P4_9") (pintype "bidirectional"))
    )
    (net (code "14") (name "Net-(LCD1-DB5)") (class "Default")
      (node (ref "LCD1") (pin "12") (pinfunction "DB5_12") (pintype "bidirectional"))
      (node (ref "U9") (pin "10") (pinfunction "P5_10") (pintype "bidirectional"))
    )
    (net (code "15") (name "Net-(LCD1-DB6)") (class "Default")
      (node (ref "LCD1") (pin "13") (pinfunction "DB6_13") (pintype "bidirectional"))
      (node (ref "U9") (pin "11") (pinfunction "P6_11") (pintype "bidirectional"))
    )
    (net (code "16") (name "Net-(LCD1-DB7)") (class "Default")
      (node (ref "LCD1") (pin "14") (pinfunction "DB7_14") (pintype "bidirectional"))
      (node (ref "U9") (pin "12") (pinfunction "P7_12") (pintype "bidirectional"))
    )
    (net (code "17") (name "Net-(LCD1-E)") (class "Default")
      (node (ref "LCD1") (pin "6") (pinfunction "E_6") (pintype "input"))
      (node (ref "U9") (pin "6") (pinfunction "P2_6") (pintype "bidirectional"))
    )
    (net (code "18") (name "Net-(LCD1-RS)") (class "Default")
      (node (ref "LCD1") (pin "4") (pinfunction "RS_4") (pintype "input"))
      (node (ref "U9") (pin "4") (pinfunction "P0_4") (pintype "bidirectional"))
    )
    (net (code "19") (name "Net-(LCD1-R{slash}W)") (class "Default")
      (node (ref "LCD1") (pin "5") (pinfunction "R/W_5") (pintype "input"))
      (node (ref "U9") (pin "5") (pinfunction "P1_5") (pintype "bidirectional"))
    )
    (net (code "20") (name "Net-(LCD1-VO)") (class "Default")
      (node (ref "LCD1") (pin "3") (pinfunction "VO_3") (pintype "bidirectional"))
      (node (ref "VR1") (pin "2") (pinfunction "WIPER_2") (pintype "passive"))
    )
    (net (code "21") (name "Net-(Q2-E)") (class "Default")
      (node (ref "D3") (pin "A") (pinfunction "A_A") (pintype "passive"))
      (node (ref "J4") (pin "2") (pinfunction "2_2") (pintype "passive"))
      (node (ref "Q2") (pin "2") (pinfunction "E_2") (pintype "passive"))
    )
    (net (code "22") (name "Net-(Q3-2)") (class "Default")
      (node (ref "C31") (pin "2") (pinfunction "2_2") (pintype "passive"))
      (node (ref "Q3") (pin "3") (pinfunction "2_3") (pintype "passive"))
      (node (ref "U8") (pin "7") (pinfunction "PB6(XTAL1/TOSC1)_7") (pintype "bidirectional"))
    )
    (net (code "23") (name "Net-(R33-Pad1)") (class "Default")
      (node (ref "R33") (pin "1") (pinfunction "1_1") (pintype "passive"))
      (node (ref "R37") (pin "1") (pinfunction "1_1") (pintype "passive"))
      (node (ref "S5") (pin "A") (pinfunction "A_A") (pintype "bidirectional"))
    )
    (net (code "24") (name "Net-(R35-Pad1)") (class "Default")
      (node (ref "R35") (pin "1") (pinfunction "1_1") (pintype "passive"))
      (node (ref "R36") (pin "1") (pinfunction "1_1") (pintype "passive"))
      (node (ref "S5") (pin "B") (pinfunction "B_B") (pintype "bidirectional"))
    )
    (net (code "25") (name "Net-(S1-1)") (class "Default")
      (node (ref "R16") (pin "2") (pinfunction "2_2") (pintype "passive"))
      (node (ref "R20") (pin "1") (pinfunction "1_1") (pintype "passive"))
      (node (ref "S1") (pin "A1") (pinfunction "1_A1") (pintype "passive"))
      (node (ref "S1") (pin "A2") (pinfunction "2_A2") (pintype "passive"))
    )
    (net (code "26") (name "Net-(S2-1)") (class "Default")
      (node (ref "R17") (pin "2") (pinfunction "2_2") (pintype "passive"))
      (node (ref "R21") (pin "1") (pinfunction "1_1") (pintype "passive"))
      (node (ref "S2") (pin "A1") (pinfunction "1_A1") (pintype "passive"))
      (node (ref "S2") (pin "A2") (pinfunction "2_A2") (pintype "passive"))
    )
    (net (code "27") (name "Net-(S3-1)") (class "Default")
      (node (ref "R25") (pin "2") (pinfunction "2_2") (pintype "passive"))
      (node (ref "R27") (pin "1") (pinfunction "1_1") (pintype "passive"))
      (node (ref "S3") (pin "A1") (pinfunction "1_A1") (pintype "passive"))
      (node (ref "S3") (pin "A2") (pinfunction "2_A2") (pintype "passive"))
    )
    (net (code "28") (name "Net-(S4-1)") (class "Default")
      (node (ref "R26") (pin "2") (pinfunction "2_2") (pintype "passive"))
      (node (ref "R28") (pin "1") (pinfunction "1_1") (pintype "passive"))
      (node (ref "S4") (pin "A1") (pinfunction "1_A1") (pintype "passive"))
      (node (ref "S4") (pin "A2") (pinfunction "2_A2") (pintype "passive"))
    )
    (net (code "29") (name "Net-(S5-SW-)") (class "Default")
      (node (ref "C35") (pin "2") (pinfunction "2_2") (pintype "passive"))
      (node (ref "R32") (pin "2") (pinfunction "2_2") (pintype "passive"))
      (node (ref "R34") (pin "1") (pinfunction "1_1") (pintype "passive"))
      (node (ref "S5") (pin "E") (pinfunction "SW-_E") (pintype "bidirectional"))
    )
    (net (code "30") (name "Net-(U1-TRIM{slash}NR)") (class "Default")
      (node (ref "C1") (pin "2") (pinfunction "2_2") (pintype "passive"))
      (node (ref "U1") (pin "5") (pinfunction "TRIM/NR_5") (pintype "passive"))
    )
    (net (code "31") (name "Net-(U2-AIN1)") (class "Default")
      (node (ref "C25") (pin "2") (pinfunction "2_2") (pintype "passive"))
      (node (ref "R13") (pin "2") (pinfunction "2_2") (pintype "passive"))
      (node (ref "U2") (pin "11") (pinfunction "AIN1_11") (pintype "passive"))
    )
    (net (code "32") (name "Net-(U2-AIN2)") (class "Default")
      (node (ref "C16") (pin "2") (pinfunction "2_2") (pintype "passive"))
      (node (ref "R2") (pin "2") (pinfunction "2_2") (pintype "passive"))
      (node (ref "U2") (pin "12") (pinfunction "AIN2_12") (pintype "passive"))
    )
    (net (code "33") (name "Net-(U3-OUT)") (class "Default")
      (node (ref "R2") (pin "1") (pinfunction "1_1") (pintype "passive"))
      (node (ref "U3") (pin "6") (pinfunction "OUT_6") (pintype "output"))
    )
    (net (code "34") (name "Net-(U5A-IN+)") (class "Default")
      (node (ref "R12") (pin "2") (pinfunction "2_2") (pintype "passive"))
      (node (ref "R8") (pin "1") (pinfunction "1_1") (pintype "passive"))
      (node (ref "U5") (pin "3") (pinfunction "IN+_3") (pintype "passive"))
    )
    (net (code "35") (name "Net-(U5A-OUT)") (class "Default")
      (node (ref "C13") (pin "1") (pinfunction "1_1") (pintype "passive"))
      (node (ref "Q1") (pin "G") (pinfunction "G_G") (pintype "passive"))
      (node (ref "U5") (pin "1") (pinfunction "OUT_1") (pintype "passive"))
    )
    (net (code "36") (name "Net-(U5B-IN+)") (class "Default")
      (node (ref "D2") (pin "C") (pinfunction "C_C") (pintype "passive"))
      (node (ref "R11") (pin "1") (pinfunction "1_1") (pintype "passive"))
      (node (ref "R5") (pin "2") (pinfunction "2_2") (pintype "passive"))
      (node (ref "U5") (pin "5") (pinfunction "IN+_5") (pintype "passive"))
    )
    (net (code "37") (name "Net-(U5B-IN-)") (class "Default")
      (node (ref "R13") (pin "1") (pinfunction "1_1") (pintype "passive"))
      (node (ref "U5") (pin "6") (pinfunction "IN-_6") (pintype "passive"))
      (node (ref "U5") (pin "7") (pinfunction "OUT_7") (pintype "passive"))
    )
    (net (code "38") (name "Net-(U6-VOUT)") (class "Default")
      (node (ref "R12") (pin "1") (pinfunction "1_1") (pintype "passive"))
      (node (ref "R7") (pin "2") (pinfunction "2_2") (pintype "passive"))
      (node (ref "U6") (pin "1") (pinfunction "VOUT_1") (pintype "passive"))
    )
    (net (code "39") (name "Net-(U7-BST)") (class "Default")
      (node (ref "C24") (pin "1") (pinfunction "1_1") (pintype "passive"))
      (node (ref "U7") (pin "8") (pinfunction "BST_8") (pintype "passive"))
    )
    (net (code "40") (name "Net-(U7-COMP)") (class "Default")
      (node (ref "R9") (pin "1") (pinfunction "1_1") (pintype "passive"))
      (node (ref "U7") (pin "3") (pinfunction "COMP_3") (pintype "output"))
    )
    (net (code "41") (name "Net-(U7-FB)") (class "Default")
      (node (ref "R3") (pin "1") (pinfunction "1_1") (pintype "passive"))
      (node (ref "R4") (pin "1") (pinfunction "1_1") (pintype "passive"))
      (node (ref "U7") (pin "4") (pinfunction "FB_4") (pintype "input"))
    )
    (net (code "42") (name "Net-(U7-FREQ)") (class "Default")
      (node (ref "R6") (pin "1") (pinfunction "1_1") (pintype "passive"))
      (node (ref "U7") (pin "6") (pinfunction "FREQ_6") (pintype "input"))
    )
    (net (code "43") (name "Net-(U7-VIN)") (class "Default")
      (node (ref "C22") (pin "1") (pinfunction "1_1") (pintype "passive"))
      (node (ref "C23") (pin "1") (pinfunction "1_1") (pintype "passive"))
      (node (ref "J2") (pin "PWR") (pinfunction "PWR_PWR") (pintype "bidirectional"))
      (node (ref "U7") (pin "7") (pinfunction "VIN_7") (pintype "input"))
    )
    (net (code "44") (name "Net-(U8-PB0(ICP))") (class "Default")
      (node (ref "R24") (pin "1") (pinfunction "1_1") (pintype "passive"))
      (node (ref "U8") (pin "12") (pinfunction "PB0(ICP)_12") (pintype "bidirectional"))
    )
    (net (code "45") (name "Net-(U8-PB1(OC1A))") (class "Default")
      (node (ref "R23") (pin "1") (pinfunction "1_1") (pintype "passive"))
      (node (ref "U8") (pin "13") (pinfunction "PB1(OC1A)_13") (pintype "bidirectional"))
    )
    (net (code "46") (name "Net-(U8-PB3(MOSI{slash}OC2))") (class "Default")
      (node (ref "J3") (pin "4") (pinfunction "4_4") (pintype "passive"))
      (node (ref "R22") (pin "1") (pinfunction "1_1") (pintype "passive"))
      (node (ref "U8") (pin "15") (pinfunction "PB3(MOSI/OC2)_15") (pintype "bidirectional"))
    )
    (net (code "47") (name "Net-(U8-PB4(MISO))") (class "Default")
      (node (ref "J3") (pin "1") (pinfunction "1_1") (pintype "passive"))
      (node (ref "R19") (pin "1") (pinfunction "1_1") (pintype "passive"))
      (node (ref "U8") (pin "16") (pinfunction "PB4(MISO)_16") (pintype "bidirectional"))
    )
    (net (code "48") (name "Net-(U8-PB5(SCK))") (class "Default")
      (node (ref "J3") (pin "3") (pinfunction "3_3") (pintype "passive"))
      (node (ref "R18") (pin "1") (pinfunction "1_1") (pintype "passive"))
      (node (ref "U8") (pin "17") (pinfunction "PB5(SCK)_17") (pintype "bidirectional"))
    )
    (net (code "49") (name "Net-(U8-PB7(XTAL2{slash}TOSC2))") (class "Default")
      (node (ref "C30") (pin "2") (pinfunction "2_2") (pintype "passive"))
      (node (ref "Q3") (pin "1") (pinfunction "1_1") (pintype "passive"))
      (node (ref "U8") (pin "8") (pinfunction "PB7(XTAL2/TOSC2)_8") (pintype "bidirectional"))
    )
    (net (code "50") (name "Net-(U8-PC4(ADC4{slash}SDA))") (class "Default")
      (node (ref "R29") (pin "1") (pinfunction "1_1") (pintype "passive"))
      (node (ref "U8") (pin "27") (pinfunction "PC4(ADC4/SDA)_27") (pintype "bidirectional"))
      (node (ref "U9") (pin "15") (pinfunction "SDA_15") (pintype "passive"))
    )
    (net (code "51") (name "Net-(U8-PC5(ADC5{slash}SCL))") (class "Default")
      (node (ref "R30") (pin "1") (pinfunction "1_1") (pintype "passive"))
      (node (ref "U8") (pin "28") (pinfunction "PC5(ADC5/SCL)_28") (pintype "bidirectional"))
      (node (ref "U9") (pin "14") (pinfunction "SCL_14") (pintype "passive"))
    )
    (net (code "52") (name "Net-(U8-PD2(INT0))") (class "Default")
      (node (ref "R32") (pin "1") (pinfunction "1_1") (pintype "passive"))
      (node (ref "U8") (pin "32") (pinfunction "PD2(INT0)_32") (pintype "bidirectional"))
    )
    (net (code "53") (name "Net-(U8-PD3(INT1))") (class "Default")
      (node (ref "C28") (pin "1") (pinfunction "1_1") (pintype "passive"))
      (node (ref "R25") (pin "1") (pinfunction "1_1") (pintype "passive"))
      (node (ref "U8") (pin "1") (pinfunction "PD3(INT1)_1") (pintype "bidirectional"))
    )
    (net (code "54") (name "Net-(U8-PD4(XCK{slash}T0))") (class "Default")
      (node (ref "C26") (pin "1") (pinfunction "1_1") (pintype "passive"))
      (node (ref "R16") (pin "1") (pinfunction "1_1") (pintype "passive"))
      (node (ref "U8") (pin "2") (pinfunction "PD4(XCK/T0)_2") (pintype "bidirectional"))
    )
    (net (code "55") (name "Net-(U8-PD5(T1))") (class "Default")
      (node (ref "C27") (pin "1") (pinfunction "1_1") (pintype "passive"))
      (node (ref "R17") (pin "1") (pinfunction "1_1") (pintype "passive"))
      (node (ref "U8") (pin "9") (pinfunction "PD5(T1)_9") (pintype "bidirectional"))
    )
    (net (code "56") (name "Net-(U8-PD6(AIN0))") (class "Default")
      (node (ref "C29") (pin "1") (pinfunction "1_1") (pintype "passive"))
      (node (ref "R26") (pin "1") (pinfunction "1_1") (pintype "passive"))
      (node (ref "U8") (pin "10") (pinfunction "PD6(AIN0)_10") (pintype "bidirectional"))
    )
    (net (code "57") (name "Net-(U10-VO)") (class "Default")
      (node (ref "C34") (pin "2") (pinfunction "2_2") (pintype "passive"))
      (node (ref "U10") (pin "2") (pinfunction "VO_2") (pintype "output"))
      (node (ref "U8") (pin "26") (pinfunction "PC3(ADC3)_26") (pintype "bidirectional"))
    )
    (net (code "58") (name "RESET") (class "Default")
      (node (ref "J3") (pin "5") (pinfunction "5_5") (pintype "passive"))
      (node (ref "R31") (pin "2") (pinfunction "2_2") (pintype "passive"))
      (node (ref "U8") (pin "29") (pinfunction "PC6(/RESET)_29") (pintype "bidirectional"))
    )
    (net (code "59") (name "ROTARY_A") (class "Default")
      (node (ref "C33") (pin "1") (pinfunction "1_1") (pintype "passive"))
      (node (ref "R33") (pin "2") (pinfunction "2_2") (pintype "passive"))
      (node (ref "U8") (pin "23") (pinfunction "PC0(ADC0)_23") (pintype "bidirectional"))
    )
    (net (code "60") (name "ROTARY_B") (class "Default")
      (node (ref "C36") (pin "1") (pinfunction "1_1") (pintype "passive"))
      (node (ref "R35") (pin "2") (pinfunction "2_2") (pintype "passive"))
      (node (ref "U8") (pin "24") (pinfunction "PC1(ADC1)_24") (pintype "bidirectional"))
    )
    (net (code "61") (name "SCLK") (class "Default")
      (node (ref "R18") (pin "2") (pinfunction "2_2") (pintype "passive"))
      (node (ref "U2") (pin "3") (pinfunction "SCLK_3") (pintype "passive"))
      (node (ref "U6") (pin "5") (pinfunction "SCLK_5") (pintype "passive"))
    )
    (net (code "62") (name "VREF") (class "Default")
      (node (ref "C19") (pin "2") (pinfunction "2_2") (pintype "passive"))
      (node (ref "C2") (pin "2") (pinfunction "2_2") (pintype "passive"))
      (node (ref "C3") (pin "2") (pinfunction "2_2") (pintype "passive"))
      (node (ref "C8") (pin "2") (pinfunction "2_2") (pintype "passive"))
      (node (ref "U1") (pin "6") (pinfunction "VOUT_6") (pintype "output"))
      (node (ref "U2") (pin "15") (pinfunction "REFIN1(+)_15") (pintype "passive"))
      (node (ref "U6") (pin "3") (pinfunction "REF_3") (pintype "passive"))
      (node (ref "U8") (pin "20") (pinfunction "AREF_20") (pintype "bidirectional"))
    )
    (net (code "63") (name "unconnected-(LCD1-DB0-Pad7)") (class "Default")
      (node (ref "LCD1") (pin "7") (pinfunction "DB0_7") (pintype "bidirectional"))
    )
    (net (code "64") (name "unconnected-(LCD1-DB1-Pad8)") (class "Default")
      (node (ref "LCD1") (pin "8") (pinfunction "DB1_8") (pintype "bidirectional"))
    )
    (net (code "65") (name "unconnected-(LCD1-DB2-Pad9)") (class "Default")
      (node (ref "LCD1") (pin "9") (pinfunction "DB2_9") (pintype "bidirectional"))
    )
    (net (code "66") (name "unconnected-(LCD1-DB3-Pad10)") (class "Default")
      (node (ref "LCD1") (pin "10") (pinfunction "DB3_10") (pintype "bidirectional"))
    )
    (net (code "67") (name "unconnected-(U1-DNC-Pad1)") (class "Default")
      (node (ref "U1") (pin "1") (pinfunction "DNC_1") (pintype "passive"))
    )
    (net (code "68") (name "unconnected-(U1-DNC-Pad8)") (class "Default")
      (node (ref "U1") (pin "8") (pinfunction "DNC_8") (pintype "passive"))
    )
    (net (code "69") (name "unconnected-(U1-NC-Pad7)") (class "Default")
      (node (ref "U1") (pin "7") (pinfunction "NC_7") (pintype "passive"))
    )
    (net (code "70") (name "unconnected-(U1-TEMP-Pad3)") (class "Default")
      (node (ref "U1") (pin "3") (pinfunction "TEMP_3") (pintype "passive"))
    )
    (net (code "71") (name "unconnected-(U2-AIN3-Pad13)") (class "Default")
      (node (ref "U2") (pin "13") (pinfunction "AIN3_13") (pintype "passive"))
    )
    (net (code "72") (name "unconnected-(U2-AIN4-Pad14)") (class "Default")
      (node (ref "U2") (pin "14") (pinfunction "AIN4_14") (pintype "passive"))
    )
    (net (code "73") (name "unconnected-(U2-BPDSW-Pad17)") (class "Default")
      (node (ref "U2") (pin "17") (pinfunction "BPDSW_17") (pintype "passive"))
    )
    (net (code "74") (name "unconnected-(U2-MCLK1-Pad1)") (class "Default")
      (node (ref "U2") (pin "1") (pinfunction "MCLK1_1") (pintype "passive"))
    )
    (net (code "75") (name "unconnected-(U2-MCLK2-Pad2)") (class "Default")
      (node (ref "U2") (pin "2") (pinfunction "MCLK2_2") (pintype "passive"))
    )
    (net (code "76") (name "unconnected-(U2-NC-Pad9)") (class "Default")
      (node (ref "U2") (pin "9") (pinfunction "NC_9") (pintype "passive"))
    )
    (net (code "77") (name "unconnected-(U2-P0{slash}REFIN2(-)-Pad8)") (class "Default")
      (node (ref "U2") (pin "8") (pinfunction "P0/REFIN2(-)_8") (pintype "passive"))
    )
    (net (code "78") (name "unconnected-(U2-P1{slash}REFIN2(+)-Pad7)") (class "Default")
      (node (ref "U2") (pin "7") (pinfunction "P1/REFIN2(+)_7") (pintype "passive"))
    )
    (net (code "79") (name "unconnected-(U2-P2-Pad6)") (class "Default")
      (node (ref "U2") (pin "6") (pinfunction "P2_6") (pintype "passive"))
    )
    (net (code "80") (name "unconnected-(U2-P3-Pad5)") (class "Default")
      (node (ref "U2") (pin "5") (pinfunction "P3_5") (pintype "passive"))
    )
    (net (code "81") (name "unconnected-(U2-~{SYNC}-Pad22)") (class "Default")
      (node (ref "U2") (pin "22") (pinfunction "~{SYNC}_22") (pintype "passive"))
    )
    (net (code "82") (name "unconnected-(U7-EN-Pad2)") (class "Default")
      (node (ref "U7") (pin "2") (pinfunction "EN_2") (pintype "input"))
    )
    (net (code "83") (name "unconnected-(U8-ADC6-Pad19)") (class "Default")
      (node (ref "U8") (pin "19") (pinfunction "ADC6_19") (pintype "bidirectional"))
    )
    (net (code "84") (name "unconnected-(U8-ADC7-Pad22)") (class "Default")
      (node (ref "U8") (pin "22") (pinfunction "ADC7_22") (pintype "bidirectional"))
    )
    (net (code "85") (name "unconnected-(U8-PB2(SS{slash}OC1B)-Pad14)") (class "Default")
      (node (ref "U8") (pin "14") (pinfunction "PB2(SS/OC1B)_14") (pintype "bidirectional"))
    )
    (net (code "86") (name "unconnected-(U8-PC2(ADC2)-Pad25)") (class "Default")
      (node (ref "U8") (pin "25") (pinfunction "PC2(ADC2)_25") (pintype "bidirectional"))
    )
    (net (code "87") (name "unconnected-(U8-PD0(RXD)-Pad30)") (class "Default")
      (node (ref "U8") (pin "30") (pinfunction "PD0(RXD)_30") (pintype "bidirectional"))
    )
    (net (code "88") (name "unconnected-(U8-PD1(TXD)-Pad31)") (class "Default")
      (node (ref "U8") (pin "31") (pinfunction "PD1(TXD)_31") (pintype "bidirectional"))
    )
    (net (code "89") (name "unconnected-(U9-P3-Pad7)") (class "Default")
      (node (ref "U9") (pin "7") (pinfunction "P3_7") (pintype "bidirectional"))
    )
    (net (code "90") (name "unconnected-(U9-~{INT}-Pad13)") (class "Default")
      (node (ref "U9") (pin "13") (pinfunction "~{INT}_13") (pintype "output"))
    )
  )
)
